# regulation-level-shifter-mk-1_2.net
KiCad netlist of a schematic drawn in EAGLE
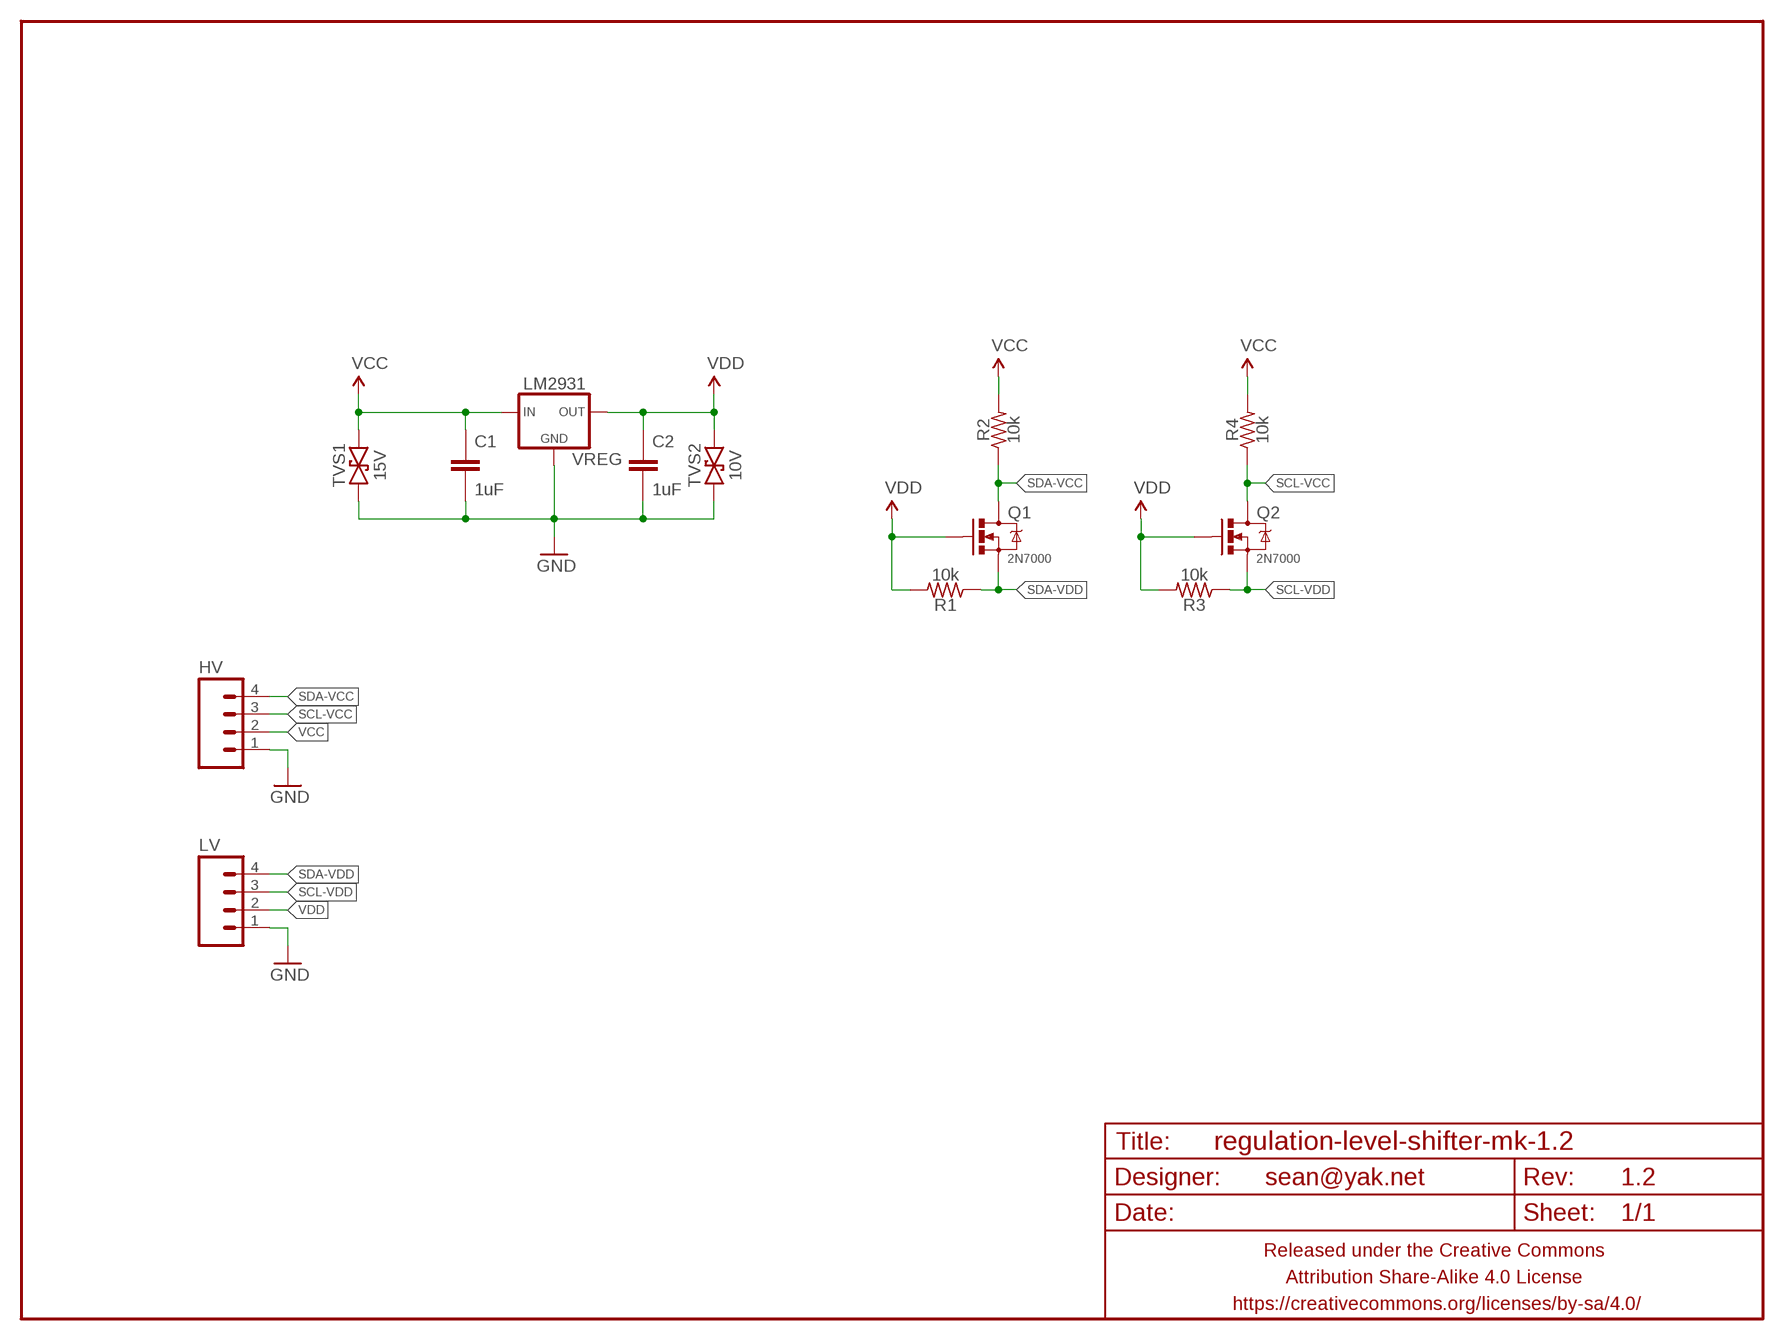
[diagram p0: schematic, sheet 1]

(export (version "E")
  (design (tool "Eeschema 10.0.6"))
  (components
    (comp (ref "C1")
      (value "1uF")
      (footprint "eagle-import:C025-024X044")
      (libsource (lib "eagle-import") (part "CAPACITOR-CERAMIC025-024X044"))
    )
    (comp (ref "C2")
      (value "1uF")
      (footprint "eagle-import:C025-024X044")
      (libsource (lib "eagle-import") (part "CAPACITOR-CERAMIC025-024X044"))
    )
    (comp (ref "FRAME1")
      (value "FRAME-LETTERNO_PACKAGE")
      (footprint "eagle-import:DUMMY")
      (fields (field (name "DESIGNER") "sean@yak.net") (field (name "VERSION") "1.2"))
      (libsource (lib "eagle-import") (part "FRAME-LETTERNO_PACKAGE"))
    )
    (comp (ref "HV")
      (value "M04PTH")
      (footprint "eagle-import:1X04-PTH-VERT")
      (libsource (lib "eagle-import") (part "M04PTH"))
    )
    (comp (ref "LV")
      (value "M04PTH")
      (footprint "eagle-import:1X04-PTH-VERT")
      (libsource (lib "eagle-import") (part "M04PTH"))
    )
    (comp (ref "Q1")
      (value "2N7000")
      (footprint "eagle-import:TO-92-AMMO")
      (libsource (lib "eagle-import") (part "MOSFET-NCHANNEL2N7000-AMMO"))
    )
    (comp (ref "Q2")
      (value "2N7000")
      (footprint "eagle-import:TO-92-AMMO")
      (libsource (lib "eagle-import") (part "MOSFET-NCHANNEL2N7000-AMMO"))
    )
    (comp (ref "R1")
      (value "10k")
      (footprint "eagle-import:RESISTOR-AXIAL-PTH-5.08MM")
      (libsource (lib "eagle-import") (part "RESISTORPTH-AXIAL-5.08MM"))
    )
    (comp (ref "R2")
      (value "10k")
      (footprint "eagle-import:RESISTOR-AXIAL-PTH-5.08MM")
      (libsource (lib "eagle-import") (part "RESISTORPTH-AXIAL-5.08MM"))
    )
    (comp (ref "R3")
      (value "10k")
      (footprint "eagle-import:RESISTOR-AXIAL-PTH-5.08MM")
      (libsource (lib "eagle-import") (part "RESISTORPTH-AXIAL-5.08MM"))
    )
    (comp (ref "R4")
      (value "10k")
      (footprint "eagle-import:RESISTOR-AXIAL-PTH-5.08MM")
      (libsource (lib "eagle-import") (part "RESISTORPTH-AXIAL-5.08MM"))
    )
    (comp (ref "TVS1")
      (value "15V")
      (footprint "eagle-import:DO-41-TVS-BI-10.16MM")
      (libsource (lib "eagle-import") (part "TVSDO-41-10.16MM"))
    )
    (comp (ref "TVS2")
      (value "10V")
      (footprint "eagle-import:DO-41-TVS-BI-10.16MM")
      (libsource (lib "eagle-import") (part "TVSDO-41-10.16MM"))
    )
    (comp (ref "VREG")
      (value "LM2931")
      (footprint "eagle-import:TO-92-AMMO")
      (libsource (lib "eagle-import") (part "V_REG_78XXTO-92-INLINE"))
    )
  )
  (nets
    (net (code "1") (name "GND") (class "Default")
      (node (ref "C1") (pin "2") (pinfunction "2_2") (pintype "passive"))
      (node (ref "C2") (pin "2") (pinfunction "2_2") (pintype "passive"))
      (node (ref "HV") (pin "1") (pinfunction "1_1") (pintype "passive"))
      (node (ref "LV") (pin "1") (pinfunction "1_1") (pintype "passive"))
      (node (ref "TVS1") (pin "P$1") (pinfunction "1_P$1") (pintype "passive"))
      (node (ref "TVS2") (pin "P$1") (pinfunction "1_P$1") (pintype "passive"))
      (node (ref "VREG") (pin "2") (pinfunction "GND_2") (pintype "bidirectional"))
    )
    (net (code "2") (name "SCL-VCC") (class "Default")
      (node (ref "HV") (pin "3") (pinfunction "3_3") (pintype "passive"))
      (node (ref "Q2") (pin "3") (pinfunction "D_3") (pintype "passive"))
      (node (ref "R4") (pin "P$1") (pinfunction "1_P$1") (pintype "passive"))
    )
    (net (code "3") (name "SCL-VDD") (class "Default")
      (node (ref "LV") (pin "3") (pinfunction "3_3") (pintype "passive"))
      (node (ref "Q2") (pin "1") (pinfunction "S_1") (pintype "passive"))
      (node (ref "R3") (pin "P$1") (pinfunction "1_P$1") (pintype "passive"))
    )
    (net (code "4") (name "SDA-VCC") (class "Default")
      (node (ref "HV") (pin "4") (pinfunction "4_4") (pintype "passive"))
      (node (ref "Q1") (pin "3") (pinfunction "D_3") (pintype "passive"))
      (node (ref "R2") (pin "P$1") (pinfunction "1_P$1") (pintype "passive"))
    )
    (net (code "5") (name "SDA-VDD") (class "Default")
      (node (ref "LV") (pin "4") (pinfunction "4_4") (pintype "passive"))
      (node (ref "Q1") (pin "1") (pinfunction "S_1") (pintype "passive"))
      (node (ref "R1") (pin "P$1") (pinfunction "1_P$1") (pintype "passive"))
    )
    (net (code "6") (name "VCC") (class "Default")
      (node (ref "C1") (pin "1") (pinfunction "1_1") (pintype "passive"))
      (node (ref "HV") (pin "2") (pinfunction "2_2") (pintype "passive"))
      (node (ref "R2") (pin "P$2") (pinfunction "2_P$2") (pintype "passive"))
      (node (ref "R4") (pin "P$2") (pinfunction "2_P$2") (pintype "passive"))
      (node (ref "TVS1") (pin "P$2") (pinfunction "2_P$2") (pintype "passive"))
      (node (ref "VREG") (pin "1") (pinfunction "IN_1") (pintype "bidirectional"))
    )
    (net (code "7") (name "VDD") (class "Default")
      (node (ref "C2") (pin "1") (pinfunction "1_1") (pintype "passive"))
      (node (ref "LV") (pin "2") (pinfunction "2_2") (pintype "passive"))
      (node (ref "Q1") (pin "2") (pinfunction "G_2") (pintype "passive"))
      (node (ref "Q2") (pin "2") (pinfunction "G_2") (pintype "passive"))
      (node (ref "R1") (pin "P$2") (pinfunction "2_P$2") (pintype "passive"))
      (node (ref "R3") (pin "P$2") (pinfunction "2_P$2") (pintype "passive"))
      (node (ref "TVS2") (pin "P$2") (pinfunction "2_P$2") (pintype "passive"))
      (node (ref "VREG") (pin "3") (pinfunction "OUT_3") (pintype "bidirectional"))
    )
  )
)
